# schematic.net
KiCad netlist of a schematic drawn in EasyEDA
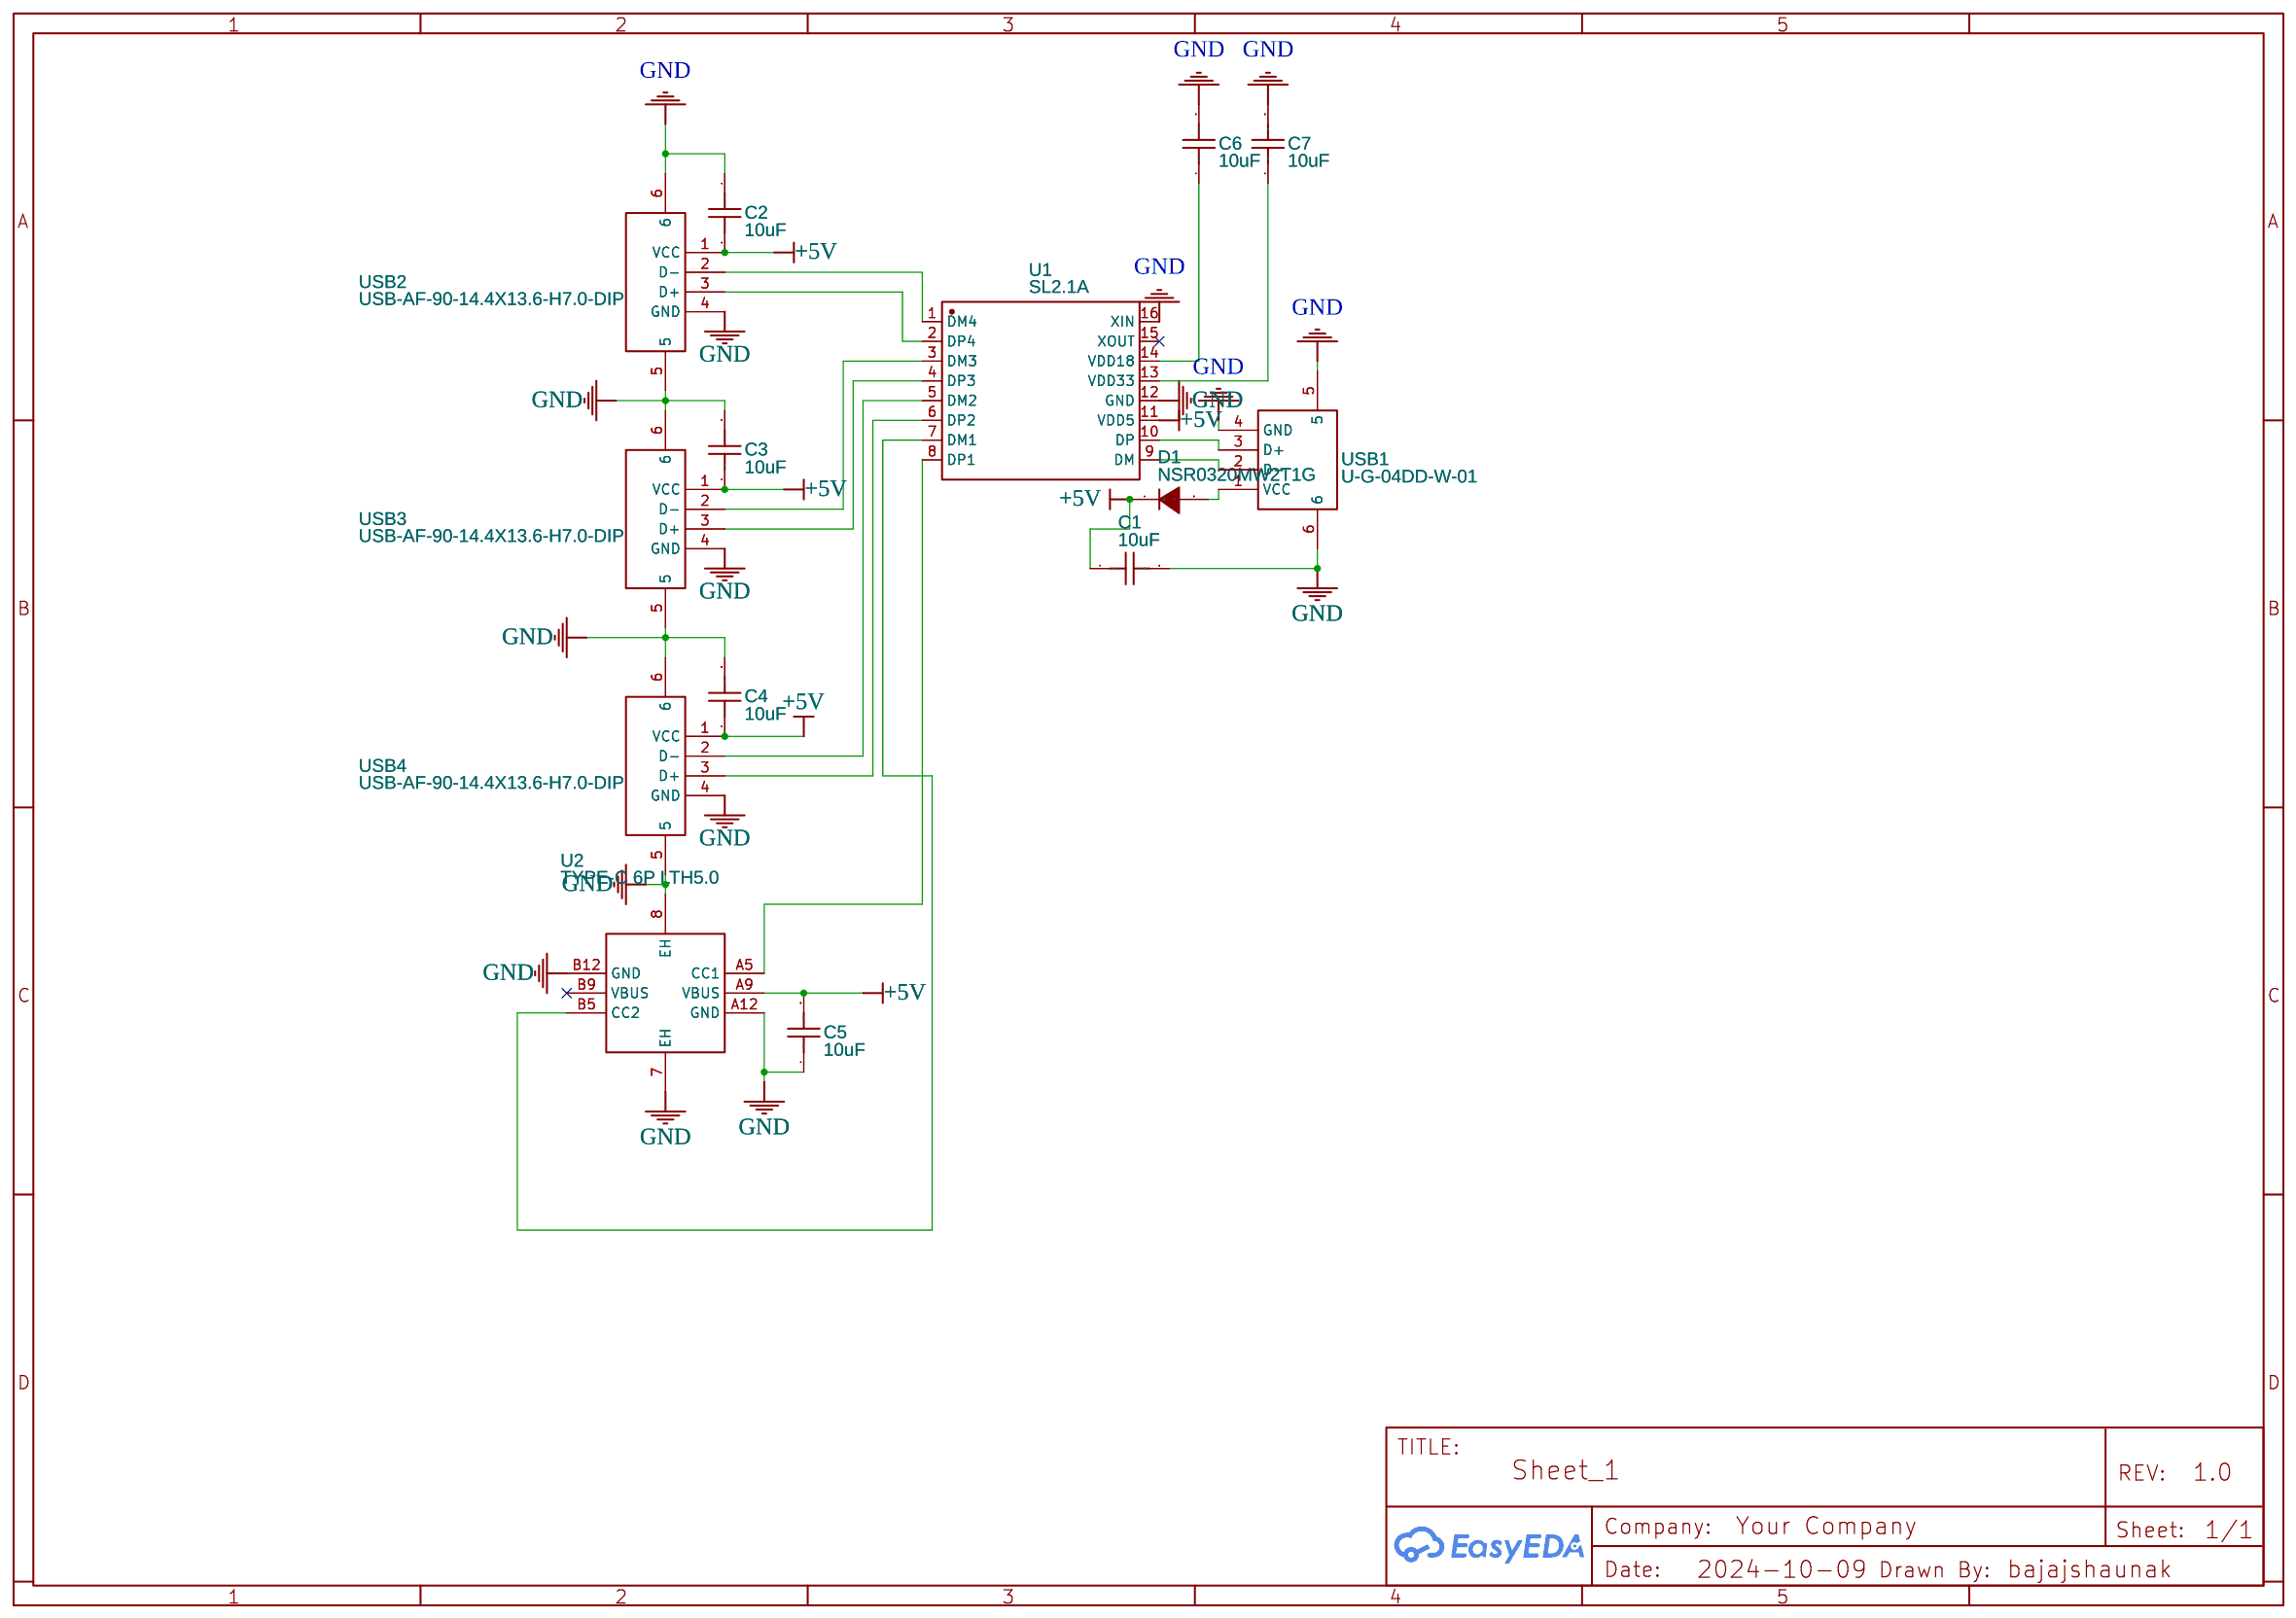
[diagram p0: schematic sheet]

(export (version "E")
  (design (tool "Eeschema 10.0.6"))
  (components
    (comp (ref "C1")
      (value "10uF")
      (fields
        (field (name "Manufacturer Part") "CL10A106KP8NNNC")
        (field (name "Manufacturer") "SAMSUNG(三星)")
      )
      (libsource (lib "") (part "CL10A106KP8NNNC"))
    )
    (comp (ref "C2")
      (value "10uF")
      (fields
        (field (name "Manufacturer Part") "CL10A106KP8NNNC")
        (field (name "Manufacturer") "SAMSUNG(三星)")
      )
      (libsource (lib "") (part "CL10A106KP8NNNC_1"))
    )
    (comp (ref "C3")
      (value "10uF")
      (fields
        (field (name "Manufacturer Part") "CL10A106KP8NNNC")
        (field (name "Manufacturer") "SAMSUNG(三星)")
      )
      (libsource (lib "") (part "CL10A106KP8NNNC_2"))
    )
    (comp (ref "C4")
      (value "10uF")
      (fields
        (field (name "Manufacturer Part") "CL10A106KP8NNNC")
        (field (name "Manufacturer") "SAMSUNG(三星)")
      )
      (libsource (lib "") (part "CL10A106KP8NNNC_2"))
    )
    (comp (ref "C5")
      (value "10uF")
      (fields
        (field (name "Manufacturer Part") "CL10A106KP8NNNC")
        (field (name "Manufacturer") "SAMSUNG(三星)")
      )
      (libsource (lib "") (part "CL10A106KP8NNNC_2"))
    )
    (comp (ref "C6")
      (value "10uF")
      (fields
        (field (name "Manufacturer Part") "CL10A106KP8NNNC")
        (field (name "Manufacturer") "SAMSUNG(三星)")
      )
      (libsource (lib "") (part "CL10A106KP8NNNC_2"))
    )
    (comp (ref "C7")
      (value "10uF")
      (fields
        (field (name "Manufacturer Part") "CL10A106KP8NNNC")
        (field (name "Manufacturer") "SAMSUNG(三星)")
      )
      (libsource (lib "") (part "CL10A106KP8NNNC_2"))
    )
    (comp (ref "D1")
      (value "NSR0320MW2T1G")
      (fields (field (name "Manufacturer") "onsemi(安森美)"))
      (libsource (lib "") (part "NSR0320MW2T1G"))
    )
    (comp (ref "U1")
      (value "SL2.1A")
      (fields (field (name "Manufacturer") "CoreChips(和芯润德)"))
      (libsource (lib "") (part "SL2.1A"))
    )
    (comp (ref "U2")
      (value "TYPE-C 6P LTH5.0")
      (fields (field (name "Manufacturer") "SHOU HAN(首韩)"))
      (libsource (lib "") (part "TYPE-C 6P LTH5.0"))
    )
    (comp (ref "USB1")
      (value "U-G-04DD-W-01")
      (fields (field (name "Manufacturer Part") "U-G-O4DD-W-1") (field (name "Manufacturer") "韩国韩荣"))
      (libsource (lib "") (part "U-G-04DD-W-01"))
    )
    (comp (ref "USB2")
      (value "USB-AF-90-14.4X13.6-H7.0-DIP")
      (fields (field (name "Manufacturer Part") "903-131A1011D10100") (field (name "Manufacturer") "精拓金"))
      (libsource (lib "") (part "USB-AF-90-14.4X13.6-H7.0-DIP"))
    )
    (comp (ref "USB3")
      (value "USB-AF-90-14.4X13.6-H7.0-DIP")
      (fields (field (name "Manufacturer Part") "903-131A1011D10100") (field (name "Manufacturer") "精拓金"))
      (libsource (lib "") (part "USB-AF-90-14.4X13.6-H7.0-DIP"))
    )
    (comp (ref "USB4")
      (value "USB-AF-90-14.4X13.6-H7.0-DIP")
      (fields (field (name "Manufacturer Part") "903-131A1011D10100") (field (name "Manufacturer") "精拓金"))
      (libsource (lib "") (part "USB-AF-90-14.4X13.6-H7.0-DIP"))
    )
  )
  (nets
    (net (code "1") (name "+5V") (class "Default")
      (node (ref "C1") (pin "1") (pinfunction "1_1") (pintype "unspecified"))
      (node (ref "C2") (pin "2") (pinfunction "2_2") (pintype "unspecified"))
      (node (ref "C3") (pin "1") (pinfunction "1_1") (pintype "unspecified"))
      (node (ref "C4") (pin "1") (pinfunction "1_1") (pintype "unspecified"))
      (node (ref "C5") (pin "2") (pinfunction "2_2") (pintype "unspecified"))
      (node (ref "D1") (pin "1") (pinfunction "C_1") (pintype "unspecified"))
      (node (ref "U1") (pin "11") (pinfunction "VDD5_11") (pintype "unspecified"))
      (node (ref "U2") (pin "A9") (pinfunction "VBUS_A9") (pintype "unspecified"))
      (node (ref "USB2") (pin "1") (pinfunction "VCC_1") (pintype "unspecified"))
      (node (ref "USB3") (pin "1") (pinfunction "VCC_1") (pintype "unspecified"))
      (node (ref "USB4") (pin "1") (pinfunction "VCC_1") (pintype "unspecified"))
    )
    (net (code "2") (name "GND") (class "Default")
      (node (ref "C1") (pin "2") (pinfunction "2_2") (pintype "unspecified"))
      (node (ref "C2") (pin "1") (pinfunction "1_1") (pintype "unspecified"))
      (node (ref "C3") (pin "2") (pinfunction "2_2") (pintype "unspecified"))
      (node (ref "C4") (pin "2") (pinfunction "2_2") (pintype "unspecified"))
      (node (ref "C5") (pin "1") (pinfunction "1_1") (pintype "unspecified"))
      (node (ref "C6") (pin "2") (pinfunction "2_2") (pintype "unspecified"))
      (node (ref "C7") (pin "2") (pinfunction "2_2") (pintype "unspecified"))
      (node (ref "U1") (pin "12") (pinfunction "GND_12") (pintype "unspecified"))
      (node (ref "U1") (pin "16") (pinfunction "XIN_16") (pintype "unspecified"))
      (node (ref "U2") (pin "7") (pinfunction "EH_7") (pintype "unspecified"))
      (node (ref "U2") (pin "8") (pinfunction "EH_8") (pintype "unspecified"))
      (node (ref "U2") (pin "A12") (pinfunction "GND_A12") (pintype "unspecified"))
      (node (ref "U2") (pin "B12") (pinfunction "GND_B12") (pintype "unspecified"))
      (node (ref "USB1") (pin "4") (pinfunction "GND_4") (pintype "unspecified"))
      (node (ref "USB1") (pin "5") (pinfunction "5_5") (pintype "unspecified"))
      (node (ref "USB1") (pin "6") (pinfunction "6_6") (pintype "unspecified"))
      (node (ref "USB2") (pin "4") (pinfunction "GND_4") (pintype "unspecified"))
      (node (ref "USB2") (pin "5") (pinfunction "5_5") (pintype "unspecified"))
      (node (ref "USB2") (pin "6") (pinfunction "6_6") (pintype "unspecified"))
      (node (ref "USB3") (pin "4") (pinfunction "GND_4") (pintype "unspecified"))
      (node (ref "USB3") (pin "5") (pinfunction "5_5") (pintype "unspecified"))
      (node (ref "USB3") (pin "6") (pinfunction "6_6") (pintype "unspecified"))
      (node (ref "USB4") (pin "4") (pinfunction "GND_4") (pintype "unspecified"))
      (node (ref "USB4") (pin "5") (pinfunction "5_5") (pintype "unspecified"))
      (node (ref "USB4") (pin "6") (pinfunction "6_6") (pintype "unspecified"))
    )
    (net (code "3") (name "Net-(D1-A)") (class "Default")
      (node (ref "D1") (pin "2") (pinfunction "A_2") (pintype "unspecified"))
      (node (ref "USB1") (pin "1") (pinfunction "VCC_1") (pintype "unspecified"))
    )
    (net (code "4") (name "Net-(U1-DM)") (class "Default")
      (node (ref "U1") (pin "9") (pinfunction "DM_9") (pintype "unspecified"))
      (node (ref "USB1") (pin "2") (pinfunction "D-_2") (pintype "unspecified"))
    )
    (net (code "5") (name "Net-(U1-DM1)") (class "Default")
      (node (ref "U1") (pin "7") (pinfunction "DM1_7") (pintype "unspecified"))
      (node (ref "U2") (pin "B5") (pinfunction "CC2_B5") (pintype "unspecified"))
    )
    (net (code "6") (name "Net-(U1-DM2)") (class "Default")
      (node (ref "U1") (pin "5") (pinfunction "DM2_5") (pintype "unspecified"))
      (node (ref "USB4") (pin "2") (pinfunction "D-_2") (pintype "unspecified"))
    )
    (net (code "7") (name "Net-(U1-DM3)") (class "Default")
      (node (ref "U1") (pin "3") (pinfunction "DM3_3") (pintype "unspecified"))
      (node (ref "USB3") (pin "2") (pinfunction "D-_2") (pintype "unspecified"))
    )
    (net (code "8") (name "Net-(U1-DM4)") (class "Default")
      (node (ref "U1") (pin "1") (pinfunction "DM4_1") (pintype "unspecified"))
      (node (ref "USB2") (pin "2") (pinfunction "D-_2") (pintype "unspecified"))
    )
    (net (code "9") (name "Net-(U1-DP)") (class "Default")
      (node (ref "U1") (pin "10") (pinfunction "DP_10") (pintype "unspecified"))
      (node (ref "USB1") (pin "3") (pinfunction "D+_3") (pintype "unspecified"))
    )
    (net (code "10") (name "Net-(U1-DP1)") (class "Default")
      (node (ref "U1") (pin "8") (pinfunction "DP1_8") (pintype "unspecified"))
      (node (ref "U2") (pin "A5") (pinfunction "CC1_A5") (pintype "unspecified"))
    )
    (net (code "11") (name "Net-(U1-DP2)") (class "Default")
      (node (ref "U1") (pin "6") (pinfunction "DP2_6") (pintype "unspecified"))
      (node (ref "USB4") (pin "3") (pinfunction "D+_3") (pintype "unspecified"))
    )
    (net (code "12") (name "Net-(U1-DP3)") (class "Default")
      (node (ref "U1") (pin "4") (pinfunction "DP3_4") (pintype "unspecified"))
      (node (ref "USB3") (pin "3") (pinfunction "D+_3") (pintype "unspecified"))
    )
    (net (code "13") (name "Net-(U1-DP4)") (class "Default")
      (node (ref "U1") (pin "2") (pinfunction "DP4_2") (pintype "unspecified"))
      (node (ref "USB2") (pin "3") (pinfunction "D+_3") (pintype "unspecified"))
    )
    (net (code "14") (name "Net-(U1-VDD18)") (class "Default")
      (node (ref "C6") (pin "1") (pinfunction "1_1") (pintype "unspecified"))
      (node (ref "U1") (pin "14") (pinfunction "VDD18_14") (pintype "unspecified"))
    )
    (net (code "15") (name "Net-(U1-VDD33)") (class "Default")
      (node (ref "C7") (pin "1") (pinfunction "1_1") (pintype "unspecified"))
      (node (ref "U1") (pin "13") (pinfunction "VDD33_13") (pintype "unspecified"))
    )
    (net (code "16") (name "unconnected-(U1-XOUT-Pad15)") (class "Default")
      (node (ref "U1") (pin "15") (pinfunction "XOUT_15") (pintype "unspecified+no_connect"))
    )
    (net (code "17") (name "unconnected-(U2-VBUS-PadB9)") (class "Default")
      (node (ref "U2") (pin "B9") (pinfunction "VBUS_B9") (pintype "unspecified+no_connect"))
    )
  )
)
